# DCS.net
KiCad netlist of a schematic drawn in EAGLE
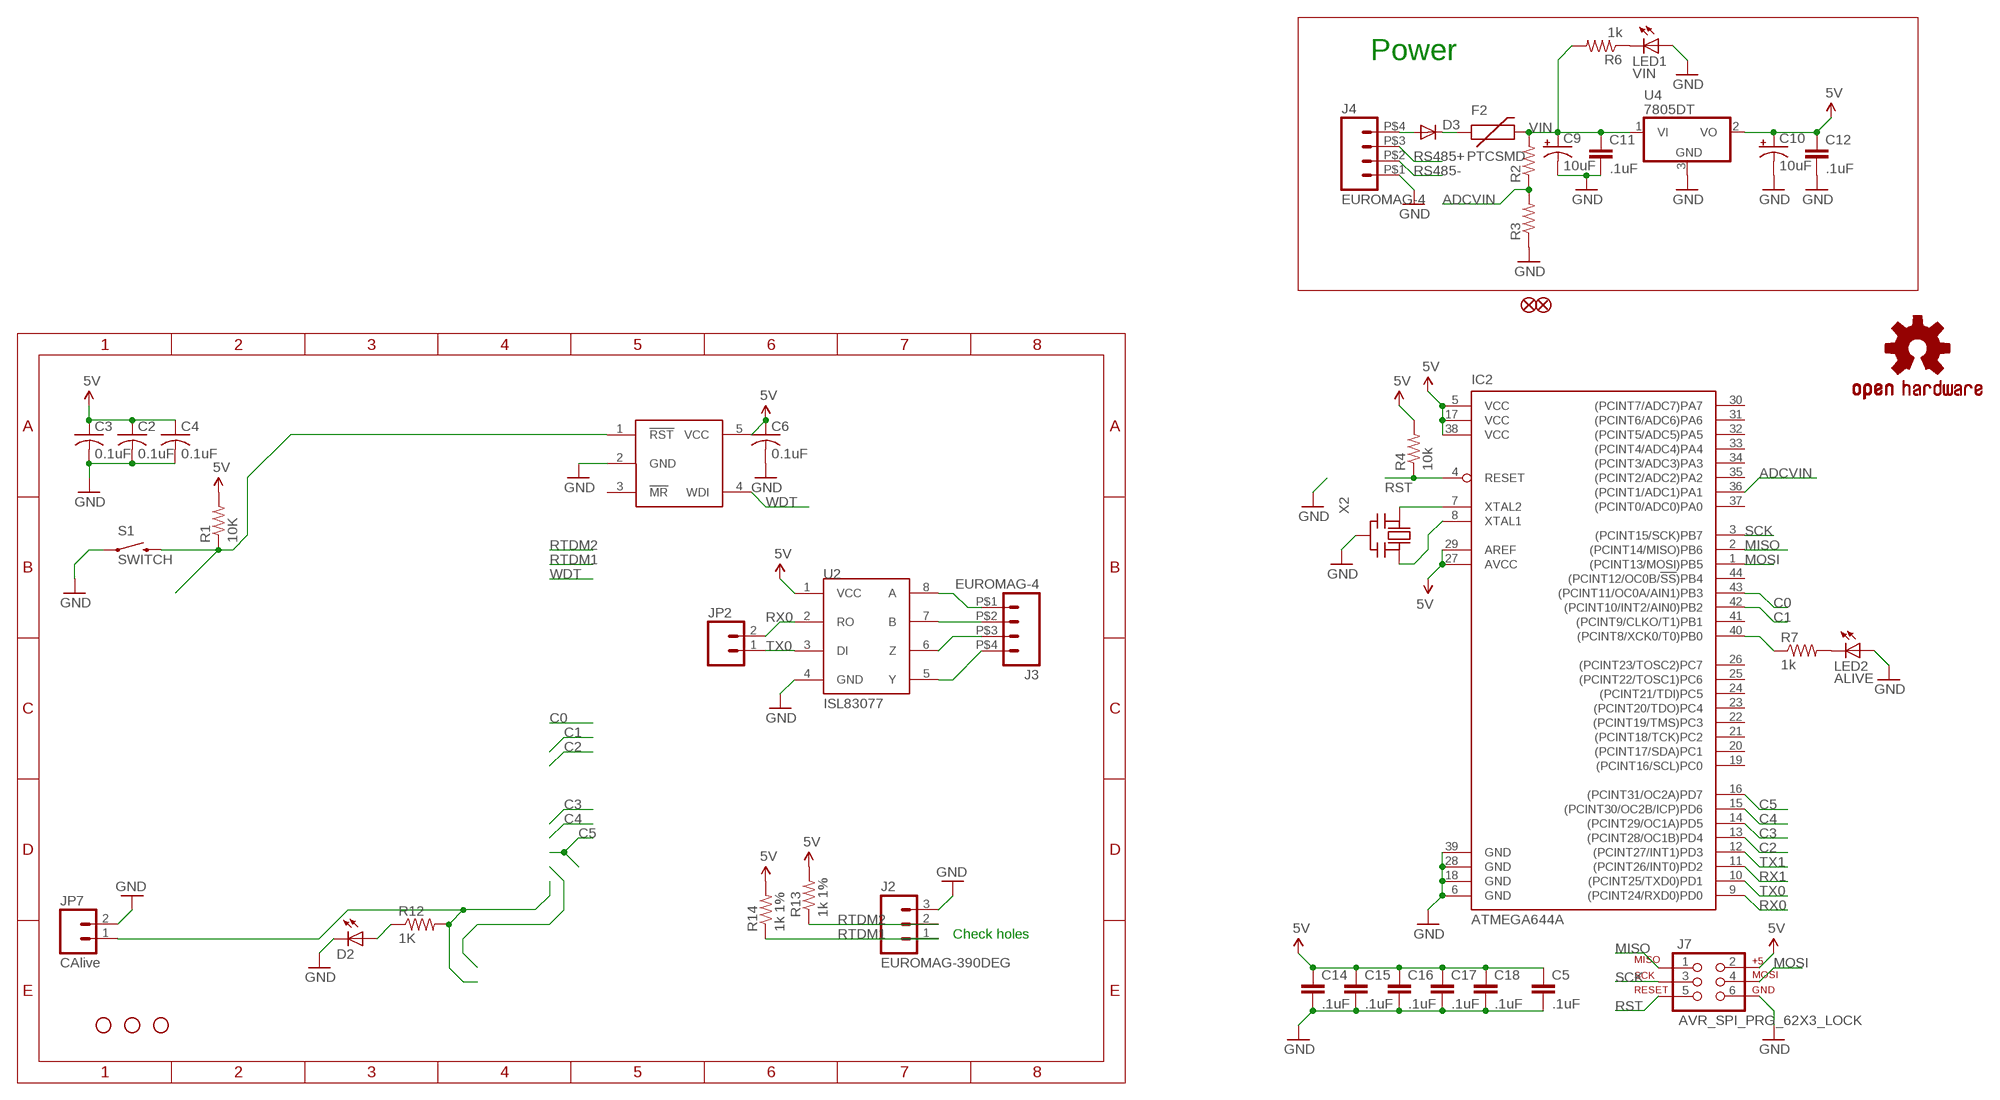
[diagram p0: schematic, sheet 1]
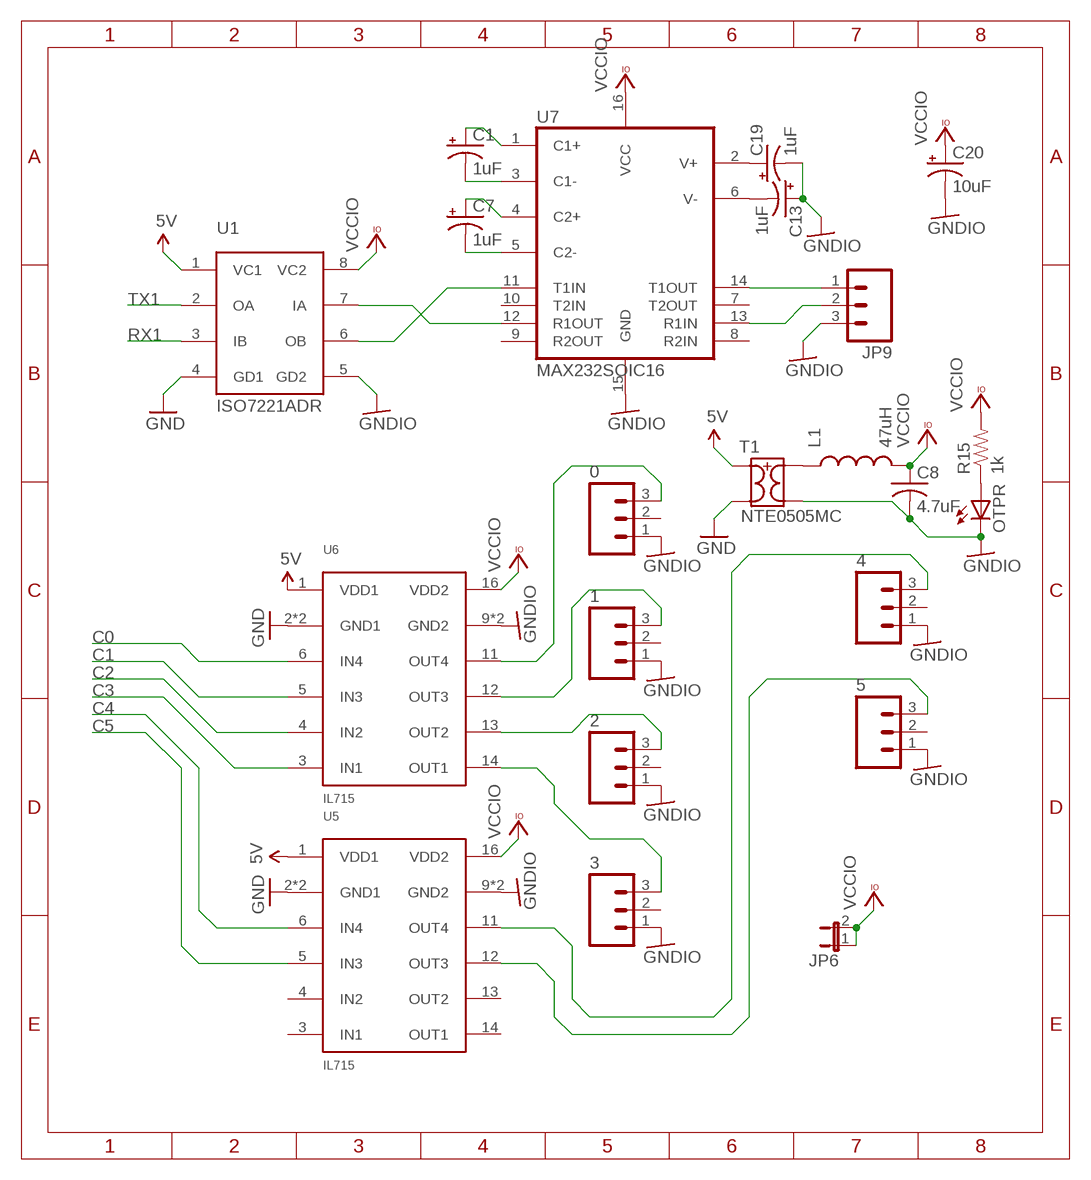
[diagram p1: schematic, sheet 2]

(export (version "E")
  (design (tool "Eeschema 10.0.6"))
  (components
    (comp (ref "0")
      (value "M03PTH")
      (footprint "eagle-import:1X03")
      (libsource (lib "eagle-import") (part "M03PTH"))
    )
    (comp (ref "1")
      (value "M03PTH")
      (footprint "eagle-import:1X03")
      (libsource (lib "eagle-import") (part "M03PTH"))
    )
    (comp (ref "2")
      (value "M03PTH")
      (footprint "eagle-import:1X03")
      (libsource (lib "eagle-import") (part "M03PTH"))
    )
    (comp (ref "3")
      (value "M03PTH")
      (footprint "eagle-import:1X03")
      (libsource (lib "eagle-import") (part "M03PTH"))
    )
    (comp (ref "4")
      (value "M03PTH")
      (footprint "eagle-import:1X03")
      (libsource (lib "eagle-import") (part "M03PTH"))
    )
    (comp (ref "5")
      (value "M03PTH")
      (footprint "eagle-import:1X03")
      (libsource (lib "eagle-import") (part "M03PTH"))
    )
    (comp (ref "C1")
      (value "1uF")
      (footprint "eagle-import:EIA3216")
      (libsource (lib "eagle-import") (part "CAP_POL1206"))
    )
    (comp (ref "C7")
      (value "1uF")
      (footprint "eagle-import:EIA3216")
      (libsource (lib "eagle-import") (part "CAP_POL1206"))
    )
    (comp (ref "C8")
      (value "4.7uF")
      (footprint "eagle-import:C0805")
      (libsource (lib "eagle-import") (part "C-USC0805"))
    )
    (comp (ref "C13")
      (value "1uF")
      (footprint "eagle-import:EIA3216")
      (libsource (lib "eagle-import") (part "CAP_POL1206"))
    )
    (comp (ref "C19")
      (value "1uF")
      (footprint "eagle-import:EIA3216")
      (libsource (lib "eagle-import") (part "CAP_POL1206"))
    )
    (comp (ref "C20")
      (value "10uF")
      (footprint "eagle-import:EIA3216")
      (libsource (lib "eagle-import") (part "CAP_POL1206"))
    )
    (comp (ref "JP6")
      (value "JUMPER-2SMD-NO")
      (footprint "eagle-import:SJ_2S-NO")
      (libsource (lib "eagle-import") (part "JUMPER-2SMD-NO"))
    )
    (comp (ref "JP9")
      (value "M03LOCK")
      (footprint "eagle-import:1X03_LOCK")
      (libsource (lib "eagle-import") (part "M03LOCK"))
    )
    (comp (ref "L1")
      (value "47uH")
      (footprint "eagle-import:0805")
      (libsource (lib "eagle-import") (part "INDUCTOR1"))
    )
    (comp (ref "OTPR")
      (value "LEDCHIP-LED0805")
      (footprint "eagle-import:CHIP-LED0805")
      (libsource (lib "eagle-import") (part "LEDCHIP-LED0805"))
    )
    (comp (ref "R15")
      (value "1k")
      (footprint "eagle-import:0805")
      (libsource (lib "eagle-import") (part "RESISTOR0805-RES"))
    )
    (comp (ref "T1")
      (value "NTE0505MC")
      (footprint "eagle-import:SO-8FT")
      (libsource (lib "eagle-import") (part "NTE0505MC"))
    )
    (comp (ref "U1")
      (value "ISO7221ADR")
      (footprint "eagle-import:SO08")
      (libsource (lib "eagle-import") (part "ISO7221ADR"))
    )
    (comp (ref "U5")
      (value "IL715")
      (footprint "eagle-import:S016")
      (libsource (lib "eagle-import") (part "IL715"))
    )
    (comp (ref "U6")
      (value "IL715")
      (footprint "eagle-import:S016")
      (libsource (lib "eagle-import") (part "IL715"))
    )
    (comp (ref "U7")
      (value "MAX232SOIC16")
      (footprint "eagle-import:SO016")
      (libsource (lib "eagle-import") (part "MAX232SOIC16"))
    )
    (comp (ref "C2")
      (value "0.1uF")
      (footprint "eagle-import:C0805")
      (libsource (lib "eagle-import") (part "C-USC0805"))
    )
    (comp (ref "C3")
      (value "0.1uF")
      (footprint "eagle-import:C0805")
      (libsource (lib "eagle-import") (part "C-USC0805"))
    )
    (comp (ref "C4")
      (value "0.1uF")
      (footprint "eagle-import:C0805")
      (libsource (lib "eagle-import") (part "C-USC0805"))
    )
    (comp (ref "C5")
      (value ".1uF")
      (footprint "eagle-import:0805")
      (libsource (lib "eagle-import") (part "CAP0805"))
    )
    (comp (ref "C6")
      (value "0.1uF")
      (footprint "eagle-import:C0805")
      (libsource (lib "eagle-import") (part "C-USC0805"))
    )
    (comp (ref "C9")
      (value "10uF")
      (footprint "eagle-import:EIA6032")
      (libsource (lib "eagle-import") (part "CAP_POL6032"))
    )
    (comp (ref "C10")
      (value "10uF")
      (footprint "eagle-import:EIA3216-KIT")
      (libsource (lib "eagle-import") (part "CAP_POL1206-KIT"))
    )
    (comp (ref "C11")
      (value ".1uF")
      (footprint "eagle-import:0805")
      (libsource (lib "eagle-import") (part "CAP0805"))
    )
    (comp (ref "C12")
      (value ".1uF")
      (footprint "eagle-import:0805")
      (libsource (lib "eagle-import") (part "CAP0805"))
    )
    (comp (ref "C14")
      (value ".1uF")
      (footprint "eagle-import:0805")
      (libsource (lib "eagle-import") (part "CAP0805"))
    )
    (comp (ref "C15")
      (value ".1uF")
      (footprint "eagle-import:0805")
      (libsource (lib "eagle-import") (part "CAP0805"))
    )
    (comp (ref "C16")
      (value ".1uF")
      (footprint "eagle-import:0805")
      (libsource (lib "eagle-import") (part "CAP0805"))
    )
    (comp (ref "C17")
      (value ".1uF")
      (footprint "eagle-import:0805")
      (libsource (lib "eagle-import") (part "CAP0805"))
    )
    (comp (ref "C18")
      (value ".1uF")
      (footprint "eagle-import:0805")
      (libsource (lib "eagle-import") (part "CAP0805"))
    )
    (comp (ref "D2")
      (value "LEDCHIPLED_0805")
      (footprint "eagle-import:CHIPLED_0805")
      (libsource (lib "eagle-import") (part "LEDCHIPLED_0805"))
    )
    (comp (ref "D3")
      (value "DIODESMA")
      (footprint "eagle-import:SMA-DIODE")
      (libsource (lib "eagle-import") (part "DIODESMA"))
    )
    (comp (ref "F2")
      (value "PTCSMD")
      (footprint "eagle-import:PTC-1206")
      (libsource (lib "eagle-import") (part "PTCSMD"))
    )
    (comp (ref "IC2")
      (value "ATMEGA644A")
      (footprint "eagle-import:TQFP44")
      (fields (field (name "MPN") "ATMEGA644PV-10AU"))
      (libsource (lib "eagle-import") (part "ATMEGA644A"))
    )
    (comp (ref "J2")
      (value "EUROMAG-390DEG")
      (footprint "eagle-import:M3")
      (libsource (lib "eagle-import") (part "EUROMAG-390DEG"))
    )
    (comp (ref "J3")
      (value "EUROMAG-4")
      (footprint "eagle-import:M4")
      (libsource (lib "eagle-import") (part "EUROMAG-4"))
    )
    (comp (ref "J4")
      (value "EUROMAG-4")
      (footprint "eagle-import:M4")
      (libsource (lib "eagle-import") (part "EUROMAG-4"))
    )
    (comp (ref "J7")
      (value "AVR_SPI_PRG_62X3_LOCK")
      (footprint "eagle-import:2X3_LOCK")
      (libsource (lib "eagle-import") (part "AVR_SPI_PRG_62X3_LOCK"))
    )
    (comp (ref "JP1")
      (value "STAND-OFF")
      (footprint "eagle-import:STAND-OFF")
      (libsource (lib "eagle-import") (part "STAND-OFF"))
    )
    (comp (ref "JP2")
      (value "M02LOCK")
      (footprint "eagle-import:1X02_LOCK")
      (libsource (lib "eagle-import") (part "M02LOCK"))
    )
    (comp (ref "JP3")
      (value "STAND-OFF")
      (footprint "eagle-import:STAND-OFF")
      (libsource (lib "eagle-import") (part "STAND-OFF"))
    )
    (comp (ref "JP4")
      (value "STAND-OFF")
      (footprint "eagle-import:STAND-OFF")
      (libsource (lib "eagle-import") (part "STAND-OFF"))
    )
    (comp (ref "JP5")
      (value "FIDUCIAL1.5X3")
      (footprint "eagle-import:FIDUCIAL-1.5X3")
      (libsource (lib "eagle-import") (part "FIDUCIAL1.5X3"))
    )
    (comp (ref "JP7")
      (value "CAlive")
      (footprint "eagle-import:MOLEX-1X2_LOCK")
      (libsource (lib "eagle-import") (part "M02POLAR_LOCK"))
    )
    (comp (ref "JP8")
      (value "FIDUCIAL1.5X3")
      (footprint "eagle-import:FIDUCIAL-1.5X3")
      (libsource (lib "eagle-import") (part "FIDUCIAL1.5X3"))
    )
    (comp (ref "LED1")
      (value "VIN")
      (footprint "eagle-import:LED-0603")
      (libsource (lib "eagle-import") (part "LED0603"))
    )
    (comp (ref "LED2")
      (value "ALIVE")
      (footprint "eagle-import:LED-0603")
      (libsource (lib "eagle-import") (part "LED0603"))
    )
    (comp (ref "R1")
      (value "10K")
      (footprint "eagle-import:M0805")
      (libsource (lib "eagle-import") (part "R-US_M0805"))
    )
    (comp (ref "R2")
      (value "RESISTOR0805-RES")
      (footprint "eagle-import:0805")
      (libsource (lib "eagle-import") (part "RESISTOR0805-RES"))
    )
    (comp (ref "R3")
      (value "RESISTOR0805-RES")
      (footprint "eagle-import:0805")
      (libsource (lib "eagle-import") (part "RESISTOR0805-RES"))
    )
    (comp (ref "R4")
      (value "10k")
      (footprint "eagle-import:0805")
      (libsource (lib "eagle-import") (part "RESISTOR0805-RES"))
    )
    (comp (ref "R6")
      (value "1k")
      (footprint "eagle-import:0805")
      (libsource (lib "eagle-import") (part "RESISTOR0805-RES"))
    )
    (comp (ref "R7")
      (value "1k")
      (footprint "eagle-import:0805")
      (libsource (lib "eagle-import") (part "RESISTOR0805-RES"))
    )
    (comp (ref "R12")
      (value "1K")
      (footprint "eagle-import:M0805")
      (libsource (lib "eagle-import") (part "R-US_M0805"))
    )
    (comp (ref "R13")
      (value "1k 1%")
      (footprint "eagle-import:M0805")
      (libsource (lib "eagle-import") (part "R-US_M0805"))
    )
    (comp (ref "R14")
      (value "1k 1%")
      (footprint "eagle-import:M0805")
      (libsource (lib "eagle-import") (part "R-US_M0805"))
    )
    (comp (ref "S1")
      (value "SWITCH")
      (footprint "eagle-import:TACTILE-PTH")
      (libsource (lib "eagle-import") (part "SWITCH-MOMENTARY-2PTH"))
    )
    (comp (ref "U$6")
      (value "OSHW-LOGOL")
      (footprint "eagle-import:OSHW-LOGO-L")
      (libsource (lib "eagle-import") (part "OSHW-LOGOL"))
    )
    (comp (ref "U2")
      (value "ISL83077")
      (footprint "eagle-import:SO08")
      (libsource (lib "eagle-import") (part "ISL83077"))
    )
    (comp (ref "U3")
      (value "MAX823")
      (footprint "eagle-import:SOT23-5L")
      (libsource (lib "eagle-import") (part "MAX823"))
    )
    (comp (ref "U4")
      (value "7805DT")
      (footprint "eagle-import:TO252")
      (libsource (lib "eagle-import") (part "78DT05"))
    )
    (comp (ref "X2")
      (value "CERMOSCILL-AWCSR")
      (footprint "eagle-import:AWCSR")
      (libsource (lib "eagle-import") (part "CERMOSCILL-AWCSR"))
    )
  )
  (nets
    (net (code "1") (name "5V") (class "Default")
      (node (ref "C10") (pin "A") (pinfunction "+_A") (pintype "passive"))
      (node (ref "C12") (pin "1") (pinfunction "1_1") (pintype "passive"))
      (node (ref "C14") (pin "1") (pinfunction "1_1") (pintype "passive"))
      (node (ref "C15") (pin "1") (pinfunction "1_1") (pintype "passive"))
      (node (ref "C16") (pin "1") (pinfunction "1_1") (pintype "passive"))
      (node (ref "C17") (pin "1") (pinfunction "1_1") (pintype "passive"))
      (node (ref "C18") (pin "1") (pinfunction "1_1") (pintype "passive"))
      (node (ref "C2") (pin "1") (pinfunction "1_1") (pintype "passive"))
      (node (ref "C3") (pin "1") (pinfunction "1_1") (pintype "passive"))
      (node (ref "C4") (pin "1") (pinfunction "1_1") (pintype "passive"))
      (node (ref "C5") (pin "1") (pinfunction "1_1") (pintype "passive"))
      (node (ref "C6") (pin "1") (pinfunction "1_1") (pintype "passive"))
      (node (ref "IC2") (pin "17") (pinfunction "VCC_17") (pintype "power_in"))
      (node (ref "IC2") (pin "27") (pinfunction "AVCC_27") (pintype "power_in"))
      (node (ref "IC2") (pin "29") (pinfunction "AREF_29") (pintype "passive"))
      (node (ref "IC2") (pin "38") (pinfunction "VCC_38") (pintype "power_in"))
      (node (ref "IC2") (pin "5") (pinfunction "VCC_5") (pintype "power_in"))
      (node (ref "J7") (pin "2") (pinfunction "2_2") (pintype "passive"))
      (node (ref "R1") (pin "2") (pinfunction "2_2") (pintype "passive"))
      (node (ref "R13") (pin "2") (pinfunction "2_2") (pintype "passive"))
      (node (ref "R14") (pin "2") (pinfunction "2_2") (pintype "passive"))
      (node (ref "R4") (pin "2") (pinfunction "2_2") (pintype "passive"))
      (node (ref "T1") (pin "3") (pinfunction "1_3") (pintype "passive"))
      (node (ref "U1") (pin "1") (pinfunction "VC1_1") (pintype "bidirectional"))
      (node (ref "U2") (pin "1") (pinfunction "VCC_1") (pintype "bidirectional"))
      (node (ref "U3") (pin "5") (pinfunction "VCC_5") (pintype "bidirectional"))
      (node (ref "U4") (pin "2") (pinfunction "VO_2") (pintype "passive"))
      (node (ref "U5") (pin "1") (pinfunction "VDD1_1") (pintype "bidirectional"))
      (node (ref "U6") (pin "1") (pinfunction "VDD1_1") (pintype "bidirectional"))
    )
    (net (code "2") (name "ADCVIN") (class "Default")
      (node (ref "IC2") (pin "36") (pinfunction "(PCINT1/ADC1)PA1_36") (pintype "bidirectional"))
      (node (ref "R2") (pin "1") (pinfunction "1_1") (pintype "passive"))
      (node (ref "R3") (pin "2") (pinfunction "2_2") (pintype "passive"))
    )
    (net (code "3") (name "C0") (class "Default")
      (node (ref "IC2") (pin "43") (pinfunction "(PCINT11/OC0A/AIN1)PB3_43") (pintype "bidirectional"))
      (node (ref "U6") (pin "6") (pinfunction "IN4_6") (pintype "bidirectional"))
    )
    (net (code "4") (name "C1") (class "Default")
      (node (ref "IC2") (pin "42") (pinfunction "(PCINT10/INT2/AIN0)PB2_42") (pintype "bidirectional"))
      (node (ref "U6") (pin "5") (pinfunction "IN3_5") (pintype "bidirectional"))
    )
    (net (code "5") (name "C2") (class "Default")
      (node (ref "IC2") (pin "13") (pinfunction "(PCINT28/OC1B)PD4_13") (pintype "bidirectional"))
      (node (ref "U6") (pin "4") (pinfunction "IN2_4") (pintype "bidirectional"))
    )
    (net (code "6") (name "C3") (class "Default")
      (node (ref "IC2") (pin "14") (pinfunction "(PCINT29/OC1A)PD5_14") (pintype "bidirectional"))
      (node (ref "U6") (pin "3") (pinfunction "IN1_3") (pintype "bidirectional"))
    )
    (net (code "7") (name "C4") (class "Default")
      (node (ref "IC2") (pin "15") (pinfunction "(PCINT30/OC2B/ICP)PD6_15") (pintype "bidirectional"))
      (node (ref "U5") (pin "6") (pinfunction "IN4_6") (pintype "bidirectional"))
    )
    (net (code "8") (name "C5") (class "Default")
      (node (ref "IC2") (pin "16") (pinfunction "(PCINT31/OC2A)PD7_16") (pintype "bidirectional"))
      (node (ref "U5") (pin "5") (pinfunction "IN3_5") (pintype "bidirectional"))
    )
    (net (code "9") (name "GND") (class "Default")
      (node (ref "C10") (pin "C") (pinfunction "-_C") (pintype "passive"))
      (node (ref "C11") (pin "2") (pinfunction "2_2") (pintype "passive"))
      (node (ref "C12") (pin "2") (pinfunction "2_2") (pintype "passive"))
      (node (ref "C14") (pin "2") (pinfunction "2_2") (pintype "passive"))
      (node (ref "C15") (pin "2") (pinfunction "2_2") (pintype "passive"))
      (node (ref "C16") (pin "2") (pinfunction "2_2") (pintype "passive"))
      (node (ref "C17") (pin "2") (pinfunction "2_2") (pintype "passive"))
      (node (ref "C18") (pin "2") (pinfunction "2_2") (pintype "passive"))
      (node (ref "C2") (pin "2") (pinfunction "2_2") (pintype "passive"))
      (node (ref "C3") (pin "2") (pinfunction "2_2") (pintype "passive"))
      (node (ref "C4") (pin "2") (pinfunction "2_2") (pintype "passive"))
      (node (ref "C5") (pin "2") (pinfunction "2_2") (pintype "passive"))
      (node (ref "C6") (pin "2") (pinfunction "2_2") (pintype "passive"))
      (node (ref "C9") (pin "P$2") (pinfunction "-_P$2") (pintype "passive"))
      (node (ref "D2") (pin "C") (pinfunction "C_C") (pintype "passive"))
      (node (ref "IC2") (pin "18") (pinfunction "GND_18") (pintype "power_in"))
      (node (ref "IC2") (pin "28") (pinfunction "GND_28") (pintype "power_in"))
      (node (ref "IC2") (pin "39") (pinfunction "GND_39") (pintype "power_in"))
      (node (ref "IC2") (pin "6") (pinfunction "GND_6") (pintype "power_in"))
      (node (ref "J2") (pin "3") (pinfunction "3_3") (pintype "passive"))
      (node (ref "J4") (pin "P$1") (pinfunction "1_P$1") (pintype "passive"))
      (node (ref "J7") (pin "6") (pinfunction "6_6") (pintype "passive"))
      (node (ref "JP7") (pin "2") (pinfunction "2_2") (pintype "passive"))
      (node (ref "LED1") (pin "A") (pinfunction "A_A") (pintype "passive"))
      (node (ref "LED2") (pin "A") (pinfunction "A_A") (pintype "passive"))
      (node (ref "R3") (pin "1") (pinfunction "1_1") (pintype "passive"))
      (node (ref "S1") (pin "1") (pinfunction "1_1") (pintype "passive"))
      (node (ref "T1") (pin "1") (pinfunction "2_1") (pintype "passive"))
      (node (ref "U1") (pin "4") (pinfunction "GD1_4") (pintype "bidirectional"))
      (node (ref "U2") (pin "4") (pinfunction "GND_4") (pintype "bidirectional"))
      (node (ref "U3") (pin "2") (pinfunction "GND_2") (pintype "bidirectional"))
      (node (ref "U4") (pin "3") (pinfunction "GND_3") (pintype "passive"))
      (node (ref "U5") (pin "2") (pinfunction "GND1_2") (pintype "bidirectional"))
      (node (ref "U5") (pin "8") (pinfunction "GND1_8") (pintype "bidirectional"))
      (node (ref "U6") (pin "2") (pinfunction "GND1_2") (pintype "bidirectional"))
      (node (ref "U6") (pin "8") (pinfunction "GND1_8") (pintype "bidirectional"))
      (node (ref "X2") (pin "2") (pinfunction "GND_2") (pintype "bidirectional"))
    )
    (net (code "10") (name "GNDIO") (class "Default")
      (node (ref "0") (pin "1") (pinfunction "1_1") (pintype "passive"))
      (node (ref "1") (pin "1") (pinfunction "1_1") (pintype "passive"))
      (node (ref "2") (pin "1") (pinfunction "1_1") (pintype "passive"))
      (node (ref "3") (pin "1") (pinfunction "1_1") (pintype "passive"))
      (node (ref "4") (pin "1") (pinfunction "1_1") (pintype "passive"))
      (node (ref "5") (pin "1") (pinfunction "1_1") (pintype "passive"))
      (node (ref "C13") (pin "A") (pinfunction "+_A") (pintype "passive"))
      (node (ref "C19") (pin "C") (pinfunction "-_C") (pintype "passive"))
      (node (ref "C20") (pin "C") (pinfunction "-_C") (pintype "passive"))
      (node (ref "C8") (pin "2") (pinfunction "2_2") (pintype "passive"))
      (node (ref "JP9") (pin "3") (pinfunction "3_3") (pintype "passive"))
      (node (ref "OTPR") (pin "C") (pinfunction "C_C") (pintype "passive"))
      (node (ref "T1") (pin "7") (pinfunction "3_7") (pintype "passive"))
      (node (ref "U1") (pin "5") (pinfunction "GD2_5") (pintype "bidirectional"))
      (node (ref "U5") (pin "15") (pinfunction "GND2_15") (pintype "bidirectional"))
      (node (ref "U5") (pin "9") (pinfunction "GND2_9") (pintype "bidirectional"))
      (node (ref "U6") (pin "15") (pinfunction "GND2_15") (pintype "bidirectional"))
      (node (ref "U6") (pin "9") (pinfunction "GND2_9") (pintype "bidirectional"))
      (node (ref "U7") (pin "15") (pinfunction "GND_15") (pintype "bidirectional"))
    )
    (net (code "11") (name "MISO") (class "Default")
      (node (ref "IC2") (pin "2") (pinfunction "(PCINT14/MISO)PB6_2") (pintype "bidirectional"))
      (node (ref "J7") (pin "1") (pinfunction "1_1") (pintype "passive"))
    )
    (net (code "12") (name "MOSI") (class "Default")
      (node (ref "IC2") (pin "1") (pinfunction "(PCINT13/MOSI)PB5_1") (pintype "bidirectional"))
      (node (ref "J7") (pin "4") (pinfunction "4_4") (pintype "passive"))
    )
    (net (code "13") (name "Net-(C1-+)") (class "Default")
      (node (ref "C1") (pin "A") (pinfunction "+_A") (pintype "passive"))
      (node (ref "U7") (pin "1") (pinfunction "C1+_1") (pintype "bidirectional"))
    )
    (net (code "14") (name "Net-(C1--)") (class "Default")
      (node (ref "C1") (pin "C") (pinfunction "-_C") (pintype "passive"))
      (node (ref "U7") (pin "3") (pinfunction "C1-_3") (pintype "bidirectional"))
    )
    (net (code "15") (name "Net-(C7-+)") (class "Default")
      (node (ref "C7") (pin "A") (pinfunction "+_A") (pintype "passive"))
      (node (ref "U7") (pin "4") (pinfunction "C2+_4") (pintype "bidirectional"))
    )
    (net (code "16") (name "Net-(C7--)") (class "Default")
      (node (ref "C7") (pin "C") (pinfunction "-_C") (pintype "passive"))
      (node (ref "U7") (pin "5") (pinfunction "C2-_5") (pintype "bidirectional"))
    )
    (net (code "17") (name "Net-(C13--)") (class "Default")
      (node (ref "C13") (pin "C") (pinfunction "-_C") (pintype "passive"))
      (node (ref "U7") (pin "6") (pinfunction "V-_6") (pintype "bidirectional"))
    )
    (net (code "18") (name "Net-(C19-+)") (class "Default")
      (node (ref "C19") (pin "A") (pinfunction "+_A") (pintype "passive"))
      (node (ref "U7") (pin "2") (pinfunction "V+_2") (pintype "bidirectional"))
    )
    (net (code "19") (name "Net-(D2-PadA)") (class "Default")
      (node (ref "D2") (pin "A") (pinfunction "A_A") (pintype "passive"))
      (node (ref "R12") (pin "1") (pinfunction "1_1") (pintype "passive"))
    )
    (net (code "20") (name "Net-(D3-PadC)") (class "Default")
      (node (ref "D3") (pin "C") (pinfunction "C_C") (pintype "passive"))
      (node (ref "F2") (pin "1") (pinfunction "1_1") (pintype "bidirectional"))
    )
    (net (code "21") (name "Net-(IC2-(PCINT8{slash}XCK0{slash}T0)PB0)") (class "Default")
      (node (ref "IC2") (pin "40") (pinfunction "(PCINT8/XCK0/T0)PB0_40") (pintype "bidirectional"))
      (node (ref "R7") (pin "1") (pinfunction "1_1") (pintype "passive"))
    )
    (net (code "22") (name "Net-(IC2-XTAL1)") (class "Default")
      (node (ref "IC2") (pin "8") (pinfunction "XTAL1_8") (pintype "bidirectional"))
      (node (ref "X2") (pin "3") (pinfunction "OUT_3") (pintype "bidirectional"))
    )
    (net (code "23") (name "Net-(IC2-XTAL2)") (class "Default")
      (node (ref "IC2") (pin "7") (pinfunction "XTAL2_7") (pintype "bidirectional"))
      (node (ref "X2") (pin "1") (pinfunction "IN_1") (pintype "bidirectional"))
    )
    (net (code "24") (name "Net-(J3-1)") (class "Default")
      (node (ref "J3") (pin "P$1") (pinfunction "1_P$1") (pintype "passive"))
      (node (ref "U2") (pin "8") (pinfunction "A_8") (pintype "bidirectional"))
    )
    (net (code "25") (name "Net-(J3-2)") (class "Default")
      (node (ref "J3") (pin "P$2") (pinfunction "2_P$2") (pintype "passive"))
      (node (ref "U2") (pin "7") (pinfunction "B_7") (pintype "bidirectional"))
    )
    (net (code "26") (name "Net-(J3-3)") (class "Default")
      (node (ref "J3") (pin "P$3") (pinfunction "3_P$3") (pintype "passive"))
      (node (ref "U2") (pin "6") (pinfunction "Z_6") (pintype "bidirectional"))
    )
    (net (code "27") (name "Net-(J3-4)") (class "Default")
      (node (ref "J3") (pin "P$4") (pinfunction "4_P$4") (pintype "passive"))
      (node (ref "U2") (pin "5") (pinfunction "Y_5") (pintype "bidirectional"))
    )
    (net (code "28") (name "Net-(J4-4)") (class "Default")
      (node (ref "D3") (pin "A") (pinfunction "A_A") (pintype "passive"))
      (node (ref "J4") (pin "P$4") (pinfunction "4_P$4") (pintype "passive"))
    )
    (net (code "29") (name "Net-(JP7-Pad1)") (class "Default")
      (node (ref "JP7") (pin "1") (pinfunction "1_1") (pintype "passive"))
      (node (ref "R12") (pin "2") (pinfunction "2_2") (pintype "passive"))
    )
    (net (code "30") (name "Net-(LED1-PadC)") (class "Default")
      (node (ref "LED1") (pin "C") (pinfunction "C_C") (pintype "passive"))
      (node (ref "R6") (pin "1") (pinfunction "1_1") (pintype "passive"))
    )
    (net (code "31") (name "Net-(LED2-PadC)") (class "Default")
      (node (ref "LED2") (pin "C") (pinfunction "C_C") (pintype "passive"))
      (node (ref "R7") (pin "2") (pinfunction "2_2") (pintype "passive"))
    )
    (net (code "32") (name "Net-(OTPR-PadA)") (class "Default")
      (node (ref "OTPR") (pin "A") (pinfunction "A_A") (pintype "passive"))
      (node (ref "R15") (pin "1") (pinfunction "1_1") (pintype "passive"))
    )
    (net (code "33") (name "Net-(S1-2)") (class "Default")
      (node (ref "R1") (pin "1") (pinfunction "1_1") (pintype "passive"))
      (node (ref "S1") (pin "3") (pinfunction "2_3") (pintype "passive"))
      (node (ref "U3") (pin "1") (pinfunction "~{RST}_1") (pintype "bidirectional"))
    )
    (net (code "34") (name "Net-(T1-4)") (class "Default")
      (node (ref "L1") (pin "1") (pinfunction "1_1") (pintype "passive"))
      (node (ref "T1") (pin "8") (pinfunction "4_8") (pintype "passive"))
    )
    (net (code "35") (name "Net-(U1-IA)") (class "Default")
      (node (ref "U1") (pin "7") (pinfunction "IA_7") (pintype "bidirectional"))
      (node (ref "U7") (pin "12") (pinfunction "R1OUT_12") (pintype "output"))
    )
    (net (code "36") (name "Net-(U1-OB)") (class "Default")
      (node (ref "U1") (pin "6") (pinfunction "OB_6") (pintype "bidirectional"))
      (node (ref "U7") (pin "11") (pinfunction "T1IN_11") (pintype "input"))
    )
    (net (code "37") (name "Net-(U5-OUT3)") (class "Default")
      (node (ref "5") (pin "3") (pinfunction "3_3") (pintype "passive"))
      (node (ref "U5") (pin "12") (pinfunction "OUT3_12") (pintype "bidirectional"))
    )
    (net (code "38") (name "Net-(U5-OUT4)") (class "Default")
      (node (ref "4") (pin "3") (pinfunction "3_3") (pintype "passive"))
      (node (ref "U5") (pin "11") (pinfunction "OUT4_11") (pintype "bidirectional"))
    )
    (net (code "39") (name "Net-(U6-OUT1)") (class "Default")
      (node (ref "3") (pin "3") (pinfunction "3_3") (pintype "passive"))
      (node (ref "U6") (pin "14") (pinfunction "OUT1_14") (pintype "bidirectional"))
    )
    (net (code "40") (name "Net-(U6-OUT2)") (class "Default")
      (node (ref "2") (pin "3") (pinfunction "3_3") (pintype "passive"))
      (node (ref "U6") (pin "13") (pinfunction "OUT2_13") (pintype "bidirectional"))
    )
    (net (code "41") (name "Net-(U6-OUT3)") (class "Default")
      (node (ref "1") (pin "3") (pinfunction "3_3") (pintype "passive"))
      (node (ref "U6") (pin "12") (pinfunction "OUT3_12") (pintype "bidirectional"))
    )
    (net (code "42") (name "Net-(U6-OUT4)") (class "Default")
      (node (ref "0") (pin "3") (pinfunction "3_3") (pintype "passive"))
      (node (ref "U6") (pin "11") (pinfunction "OUT4_11") (pintype "bidirectional"))
    )
    (net (code "43") (name "Net-(U7-R1IN)") (class "Default")
      (node (ref "JP9") (pin "2") (pinfunction "2_2") (pintype "passive"))
      (node (ref "U7") (pin "13") (pinfunction "R1IN_13") (pintype "input"))
    )
    (net (code "44") (name "Net-(U7-T1OUT)") (class "Default")
      (node (ref "JP9") (pin "1") (pinfunction "1_1") (pintype "passive"))
      (node (ref "U7") (pin "14") (pinfunction "T1OUT_14") (pintype "output"))
    )
    (net (code "45") (name "RS485+") (class "Default")
      (node (ref "J4") (pin "P$3") (pinfunction "3_P$3") (pintype "passive"))
    )
    (net (code "46") (name "RS485-") (class "Default")
      (node (ref "J4") (pin "P$2") (pinfunction "2_P$2") (pintype "passive"))
    )
    (net (code "47") (name "RST") (class "Default")
      (node (ref "IC2") (pin "4") (pinfunction "RESET_4") (pintype "input"))
      (node (ref "J7") (pin "5") (pinfunction "5_5") (pintype "passive"))
      (node (ref "R4") (pin "1") (pinfunction "1_1") (pintype "passive"))
    )
    (net (code "48") (name "RTDM1") (class "Default")
      (node (ref "J2") (pin "1") (pinfunction "1_1") (pintype "passive"))
      (node (ref "R14") (pin "1") (pinfunction "1_1") (pintype "passive"))
    )
    (net (code "49") (name "RTDM2") (class "Default")
      (node (ref "J2") (pin "2") (pinfunction "2_2") (pintype "passive"))
      (node (ref "R13") (pin "1") (pinfunction "1_1") (pintype "passive"))
    )
    (net (code "50") (name "RX0") (class "Default")
      (node (ref "IC2") (pin "9") (pinfunction "(PCINT24/RXD0)PD0_9") (pintype "bidirectional"))
      (node (ref "JP2") (pin "2") (pinfunction "2_2") (pintype "passive"))
      (node (ref "U2") (pin "2") (pinfunction "RO_2") (pintype "bidirectional"))
    )
    (net (code "51") (name "RX1") (class "Default")
      (node (ref "IC2") (pin "11") (pinfunction "(PCINT26/INT0)PD2_11") (pintype "bidirectional"))
      (node (ref "U1") (pin "3") (pinfunction "IB_3") (pintype "bidirectional"))
    )
    (net (code "52") (name "SCK") (class "Default")
      (node (ref "IC2") (pin "3") (pinfunction "(PCINT15/SCK)PB7_3") (pintype "bidirectional"))
      (node (ref "J7") (pin "3") (pinfunction "3_3") (pintype "passive"))
    )
    (net (code "53") (name "TX0") (class "Default")
      (node (ref "IC2") (pin "10") (pinfunction "(PCINT25/TXD0)PD1_10") (pintype "bidirectional"))
      (node (ref "JP2") (pin "1") (pinfunction "1_1") (pintype "passive"))
      (node (ref "U2") (pin "3") (pinfunction "DI_3") (pintype "bidirectional"))
    )
    (net (code "54") (name "TX1") (class "Default")
      (node (ref "IC2") (pin "12") (pinfunction "(PCINT27/INT1)PD3_12") (pintype "bidirectional"))
      (node (ref "U1") (pin "2") (pinfunction "OA_2") (pintype "bidirectional"))
    )
    (net (code "55") (name "VCCIO") (class "Default")
      (node (ref "C20") (pin "A") (pinfunction "+_A") (pintype "passive"))
      (node (ref "C8") (pin "1") (pinfunction "1_1") (pintype "passive"))
      (node (ref "JP6") (pin "1") (pinfunction "1_1") (pintype "passive"))
      (node (ref "JP6") (pin "2") (pinfunction "2_2") (pintype "passive"))
      (node (ref "L1") (pin "2") (pinfunction "2_2") (pintype "passive"))
      (node (ref "R15") (pin "2") (pinfunction "2_2") (pintype "passive"))
      (node (ref "U1") (pin "8") (pinfunction "VC2_8") (pintype "bidirectional"))
      (node (ref "U5") (pin "16") (pinfunction "VDD2_16") (pintype "bidirectional"))
      (node (ref "U6") (pin "16") (pinfunction "VDD2_16") (pintype "bidirectional"))
      (node (ref "U7") (pin "16") (pinfunction "VCC_16") (pintype "bidirectional"))
    )
    (net (code "56") (name "VIN") (class "Default")
      (node (ref "C11") (pin "1") (pinfunction "1_1") (pintype "passive"))
      (node (ref "C9") (pin "P$1") (pinfunction "+_P$1") (pintype "passive"))
      (node (ref "F2") (pin "2") (pinfunction "2_2") (pintype "bidirectional"))
      (node (ref "R2") (pin "2") (pinfunction "2_2") (pintype "passive"))
      (node (ref "R6") (pin "2") (pinfunction "2_2") (pintype "passive"))
      (node (ref "U4") (pin "1") (pinfunction "VI_1") (pintype "input"))
    )
    (net (code "57") (name "WDT") (class "Default")
      (node (ref "U3") (pin "4") (pinfunction "WDI_4") (pintype "bidirectional"))
    )
    (net (code "58") (name "unconnected-(0-Pad2)") (class "Default")
      (node (ref "0") (pin "2") (pinfunction "2_2") (pintype "passive"))
    )
    (net (code "59") (name "unconnected-(1-Pad2)") (class "Default")
      (node (ref "1") (pin "2") (pinfunction "2_2") (pintype "passive"))
    )
    (net (code "60") (name "unconnected-(2-Pad2)") (class "Default")
      (node (ref "2") (pin "2") (pinfunction "2_2") (pintype "passive"))
    )
    (net (code "61") (name "unconnected-(3-Pad2)") (class "Default")
      (node (ref "3") (pin "2") (pinfunction "2_2") (pintype "passive"))
    )
    (net (code "62") (name "unconnected-(4-Pad2)") (class "Default")
      (node (ref "4") (pin "2") (pinfunction "2_2") (pintype "passive"))
    )
    (net (code "63") (name "unconnected-(5-Pad2)") (class "Default")
      (node (ref "5") (pin "2") (pinfunction "2_2") (pintype "passive"))
    )
    (net (code "64") (name "unconnected-(IC2-(PCINT0{slash}ADC0)PA0-Pad37)") (class "Default")
      (node (ref "IC2") (pin "37") (pinfunction "(PCINT0/ADC0)PA0_37") (pintype "bidirectional"))
    )
    (net (code "65") (name "unconnected-(IC2-(PCINT2{slash}ADC2)PA2-Pad35)") (class "Default")
      (node (ref "IC2") (pin "35") (pinfunction "(PCINT2/ADC2)PA2_35") (pintype "bidirectional"))
    )
    (net (code "66") (name "unconnected-(IC2-(PCINT3{slash}ADC3)PA3-Pad34)") (class "Default")
      (node (ref "IC2") (pin "34") (pinfunction "(PCINT3/ADC3)PA3_34") (pintype "bidirectional"))
    )
    (net (code "67") (name "unconnected-(IC2-(PCINT4{slash}ADC4)PA4-Pad33)") (class "Default")
      (node (ref "IC2") (pin "33") (pinfunction "(PCINT4/ADC4)PA4_33") (pintype "bidirectional"))
    )
    (net (code "68") (name "unconnected-(IC2-(PCINT5{slash}ADC5)PA5-Pad32)") (class "Default")
      (node (ref "IC2") (pin "32") (pinfunction "(PCINT5/ADC5)PA5_32") (pintype "bidirectional"))
    )
    (net (code "69") (name "unconnected-(IC2-(PCINT6{slash}ADC6)PA6-Pad31)") (class "Default")
      (node (ref "IC2") (pin "31") (pinfunction "(PCINT6/ADC6)PA6_31") (pintype "bidirectional"))
    )
    (net (code "70") (name "unconnected-(IC2-(PCINT7{slash}ADC7)PA7-Pad30)") (class "Default")
      (node (ref "IC2") (pin "30") (pinfunction "(PCINT7/ADC7)PA7_30") (pintype "bidirectional"))
    )
    (net (code "71") (name "unconnected-(IC2-(PCINT9{slash}CLKO{slash}T1)PB1-Pad41)") (class "Default")
      (node (ref "IC2") (pin "41") (pinfunction "(PCINT9/CLKO/T1)PB1_41") (pintype "bidirectional"))
    )
    (net (code "72") (name "unconnected-(IC2-(PCINT12{slash}OC0B{slash}~{SS})PB4-Pad44)") (class "Default")
      (node (ref "IC2") (pin "44") (pinfunction "(PCINT12/OC0B/~{SS})PB4_44") (pintype "bidirectional"))
    )
    (net (code "73") (name "unconnected-(IC2-(PCINT16{slash}SCL)PC0-Pad19)") (class "Default")
      (node (ref "IC2") (pin "19") (pinfunction "(PCINT16/SCL)PC0_19") (pintype "output"))
    )
    (net (code "74") (name "unconnected-(IC2-(PCINT17{slash}SDA)PC1-Pad20)") (class "Default")
      (node (ref "IC2") (pin "20") (pinfunction "(PCINT17/SDA)PC1_20") (pintype "output"))
    )
    (net (code "75") (name "unconnected-(IC2-(PCINT18{slash}TCK)PC2-Pad21)") (class "Default")
      (node (ref "IC2") (pin "21") (pinfunction "(PCINT18/TCK)PC2_21") (pintype "output"))
    )
    (net (code "76") (name "unconnected-(IC2-(PCINT19{slash}TMS)PC3-Pad22)") (class "Default")
      (node (ref "IC2") (pin "22") (pinfunction "(PCINT19/TMS)PC3_22") (pintype "output"))
    )
    (net (code "77") (name "unconnected-(IC2-(PCINT20{slash}TDO)PC4-Pad23)") (class "Default")
      (node (ref "IC2") (pin "23") (pinfunction "(PCINT20/TDO)PC4_23") (pintype "output"))
    )
    (net (code "78") (name "unconnected-(IC2-(PCINT21{slash}TDI)PC5-Pad24)") (class "Default")
      (node (ref "IC2") (pin "24") (pinfunction "(PCINT21/TDI)PC5_24") (pintype "output"))
    )
    (net (code "79") (name "unconnected-(IC2-(PCINT22{slash}TOSC1)PC6-Pad25)") (class "Default")
      (node (ref "IC2") (pin "25") (pinfunction "(PCINT22/TOSC1)PC6_25") (pintype "output"))
    )
    (net (code "80") (name "unconnected-(IC2-(PCINT23{slash}TOSC2)PC7-Pad26)") (class "Default")
      (node (ref "IC2") (pin "26") (pinfunction "(PCINT23/TOSC2)PC7_26") (pintype "output"))
    )
    (net (code "81") (name "unconnected-(U3-~{MR}-Pad3)") (class "Default")
      (node (ref "U3") (pin "3") (pinfunction "~{MR}_3") (pintype "bidirectional"))
    )
    (net (code "82") (name "unconnected-(U5-IN1-Pad3)") (class "Default")
      (node (ref "U5") (pin "3") (pinfunction "IN1_3") (pintype "bidirectional"))
    )
    (net (code "83") (name "unconnected-(U5-IN2-Pad4)") (class "Default")
      (node (ref "U5") (pin "4") (pinfunction "IN2_4") (pintype "bidirectional"))
    )
    (net (code "84") (name "unconnected-(U5-OUT1-Pad14)") (class "Default")
      (node (ref "U5") (pin "14") (pinfunction "OUT1_14") (pintype "bidirectional"))
    )
    (net (code "85") (name "unconnected-(U5-OUT2-Pad13)") (class "Default")
      (node (ref "U5") (pin "13") (pinfunction "OUT2_13") (pintype "bidirectional"))
    )
    (net (code "86") (name "unconnected-(U7-R2IN-Pad8)") (class "Default")
      (node (ref "U7") (pin "8") (pinfunction "R2IN_8") (pintype "input"))
    )
    (net (code "87") (name "unconnected-(U7-R2OUT-Pad9)") (class "Default")
      (node (ref "U7") (pin "9") (pinfunction "R2OUT_9") (pintype "output"))
    )
    (net (code "88") (name "unconnected-(U7-T2IN-Pad10)") (class "Default")
      (node (ref "U7") (pin "10") (pinfunction "T2IN_10") (pintype "input"))
    )
    (net (code "89") (name "unconnected-(U7-T2OUT-Pad7)") (class "Default")
      (node (ref "U7") (pin "7") (pinfunction "T2OUT_7") (pintype "output"))
    )
  )
)
